# Ports.net
KiCad netlist of a schematic drawn in Altium Designer
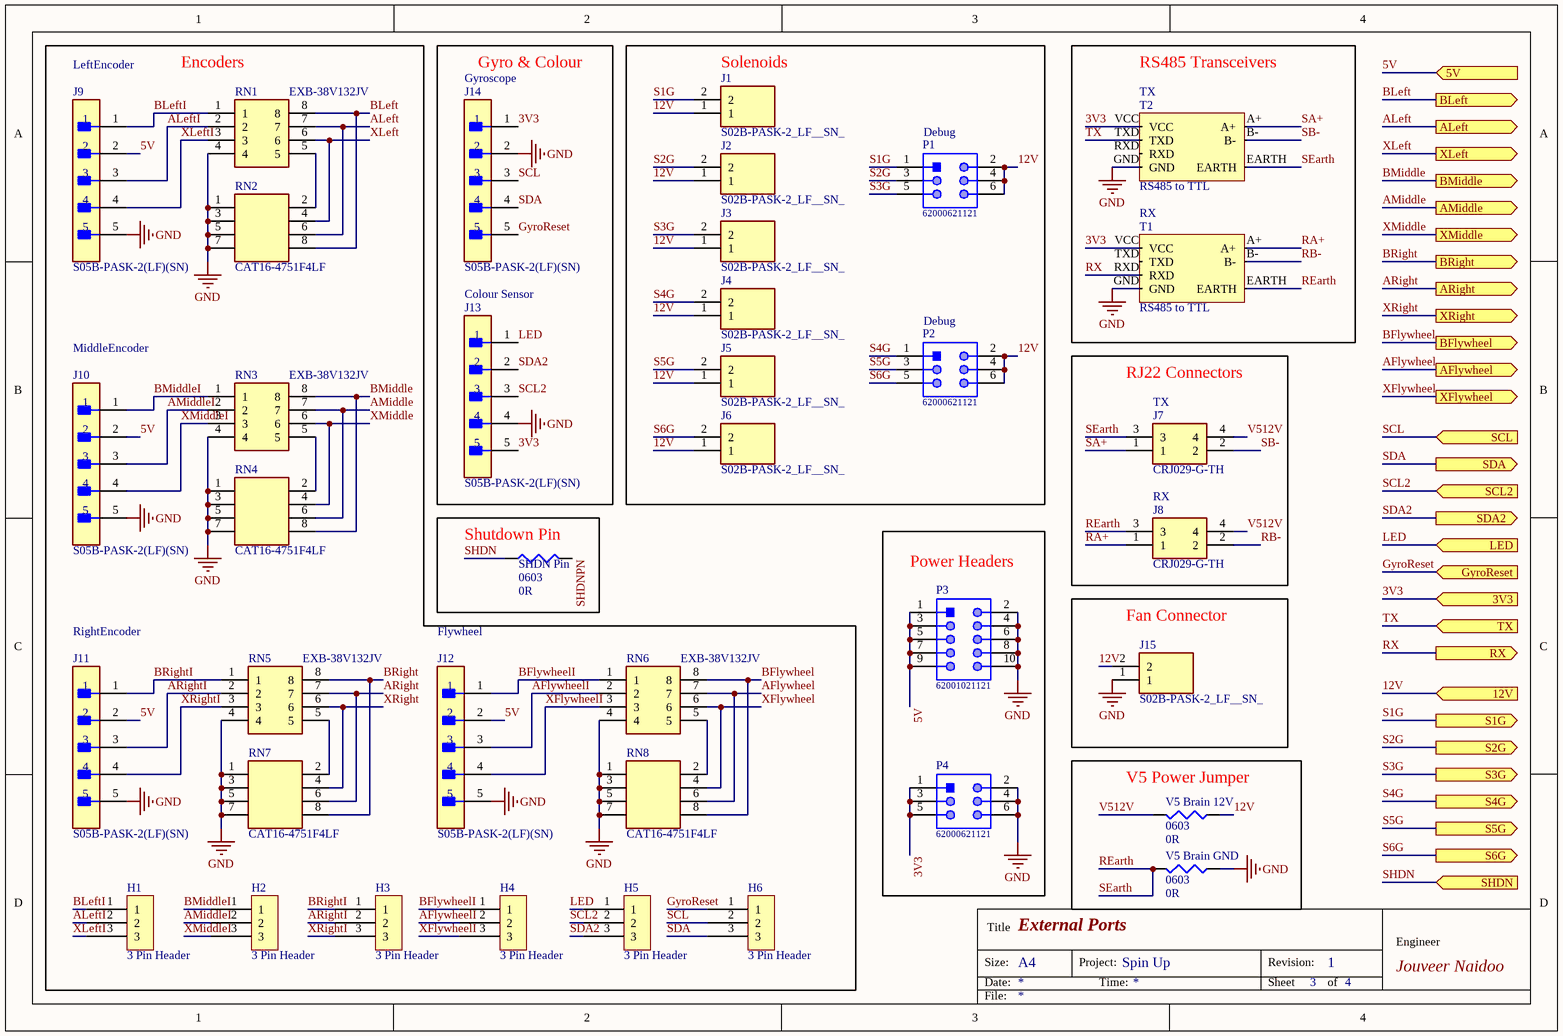
[diagram p0: Ports.SchDoc]

(export (version "E")
  (design (tool "Eeschema 10.0.6"))
  (components
    (comp (ref "H1")
      (value "3 Pin Header")
      (footprint "3 Pin Header-Footprint-1")
      (libsource (lib "Jouveer") (part "3 Pin Header"))
    )
    (comp (ref "H2")
      (value "3 Pin Header")
      (footprint "3 Pin Header-Footprint-1")
      (libsource (lib "Jouveer") (part "3 Pin Header"))
    )
    (comp (ref "H3")
      (value "3 Pin Header")
      (footprint "3 Pin Header-Footprint-1")
      (libsource (lib "Jouveer") (part "3 Pin Header"))
    )
    (comp (ref "H4")
      (value "3 Pin Header")
      (footprint "3 Pin Header-Footprint-1")
      (libsource (lib "Jouveer") (part "3 Pin Header"))
    )
    (comp (ref "H5")
      (value "3 Pin Header")
      (footprint "3 Pin Header-Footprint-1")
      (libsource (lib "Jouveer") (part "3 Pin Header"))
    )
    (comp (ref "H6")
      (value "3 Pin Header")
      (footprint "3 Pin Header-Footprint-1")
      (libsource (lib "Jouveer") (part "3 Pin Header"))
    )
    (comp (ref "J1")
      (value "S02B-PASK-2_LF__SN_")
      (footprint "SamacSys:S02BPASK2LFSN")
      (description "Connector")
      (fields (field (name "MANUFACTURER_PART_NUMBER") "S02B-PASK-2(LF)(SN)"))
      (libsource (lib "*") (part "S02B-PASK-2_LF__SN_"))
    )
    (comp (ref "J2")
      (value "S02B-PASK-2_LF__SN_")
      (footprint "SamacSys:S02BPASK2LFSN")
      (description "Connector")
      (fields (field (name "MANUFACTURER_PART_NUMBER") "S02B-PASK-2(LF)(SN)"))
      (libsource (lib "*") (part "S02B-PASK-2_LF__SN_"))
    )
    (comp (ref "J3")
      (value "S02B-PASK-2_LF__SN_")
      (footprint "SamacSys:S02BPASK2LFSN")
      (description "Connector")
      (fields (field (name "MANUFACTURER_PART_NUMBER") "S02B-PASK-2(LF)(SN)"))
      (libsource (lib "*") (part "S02B-PASK-2_LF__SN_"))
    )
    (comp (ref "J4")
      (value "S02B-PASK-2_LF__SN_")
      (footprint "SamacSys:S02BPASK2LFSN")
      (description "Connector")
      (fields (field (name "MANUFACTURER_PART_NUMBER") "S02B-PASK-2(LF)(SN)"))
      (libsource (lib "*") (part "S02B-PASK-2_LF__SN_"))
    )
    (comp (ref "J5")
      (value "S02B-PASK-2_LF__SN_")
      (footprint "SamacSys:S02BPASK2LFSN")
      (description "Connector")
      (fields (field (name "MANUFACTURER_PART_NUMBER") "S02B-PASK-2(LF)(SN)"))
      (libsource (lib "*") (part "S02B-PASK-2_LF__SN_"))
    )
    (comp (ref "J6")
      (value "S02B-PASK-2_LF__SN_")
      (footprint "SamacSys:S02BPASK2LFSN")
      (description "Connector")
      (fields (field (name "MANUFACTURER_PART_NUMBER") "S02B-PASK-2(LF)(SN)"))
      (libsource (lib "*") (part "S02B-PASK-2_LF__SN_"))
    )
    (comp (ref "J7")
      (value "CRJ029-G-TH")
      (footprint "SamacSys:CRJ029GTH")
      (description "Connector")
      (fields (field (name "MOUSER PART NUMBER") "490-CRJ029-G-TH"))
      (libsource (lib "*") (part "CRJ029-G-TH"))
    )
    (comp (ref "J8")
      (value "CRJ029-G-TH")
      (footprint "SamacSys:CRJ029GTH")
      (description "Connector")
      (fields (field (name "MOUSER PART NUMBER") "490-CRJ029-G-TH"))
      (libsource (lib "*") (part "CRJ029-G-TH"))
    )
    (comp (ref "J9")
      (value "S05B-PASK-2(LF)(SN)")
      (footprint "FP-S05B-PASK-2_LF_SN-MFG")
      (description "CONN HEADER R/A 5POS 2MM")
      (libsource (lib "Altium Content Vault") (part "bf93c07fd2649a848d0ec8585582aab"))
    )
    (comp (ref "J10")
      (value "S05B-PASK-2(LF)(SN)")
      (footprint "FP-S05B-PASK-2_LF_SN-MFG")
      (description "CONN HEADER R/A 5POS 2MM")
      (libsource (lib "Altium Content Vault") (part "bf93c07fd2649a848d0ec8585582aab"))
    )
    (comp (ref "J11")
      (value "S05B-PASK-2(LF)(SN)")
      (footprint "FP-S05B-PASK-2_LF_SN-MFG")
      (description "CONN HEADER R/A 5POS 2MM")
      (libsource (lib "Altium Content Vault") (part "bf93c07fd2649a848d0ec8585582aab"))
    )
    (comp (ref "J12")
      (value "S05B-PASK-2(LF)(SN)")
      (footprint "FP-S05B-PASK-2_LF_SN-MFG")
      (description "CONN HEADER R/A 5POS 2MM")
      (libsource (lib "Altium Content Vault") (part "bf93c07fd2649a848d0ec8585582aab"))
    )
    (comp (ref "J13")
      (value "S05B-PASK-2(LF)(SN)")
      (footprint "FP-S05B-PASK-2_LF_SN-MFG")
      (description "CONN HEADER R/A 5POS 2MM")
      (libsource (lib "Altium Content Vault") (part "bf93c07fd2649a848d0ec8585582aab"))
    )
    (comp (ref "J14")
      (value "S05B-PASK-2(LF)(SN)")
      (footprint "FP-S05B-PASK-2_LF_SN-MFG")
      (description "CONN HEADER R/A 5POS 2MM")
      (libsource (lib "Altium Content Vault") (part "bf93c07fd2649a848d0ec8585582aab"))
    )
    (comp (ref "J15")
      (value "S02B-PASK-2_LF__SN_")
      (footprint "SamacSys:S02BPASK2LFSN")
      (description "Connector")
      (fields (field (name "MANUFACTURER_PART_NUMBER") "S02B-PASK-2(LF)(SN)"))
      (libsource (lib "*") (part "S02B-PASK-2_LF__SN_"))
    )
    (comp (ref "P1")
      (value "62000621121")
      (footprint "62000621121")
      (description "THT Vertical Pin Header WR-PHD, Pitch 2.00 mm, Dual Row, 6 pins")
      (fields (field (name "MANUFACTURER") "Wurth Elektronik") (field (name "PUBLISHER") "WurthElektronik"))
      (libsource (lib "Altium Content Vault") (part "WE-CN-2P-M-R6"))
    )
    (comp (ref "P2")
      (value "62000621121")
      (footprint "62000621121")
      (description "THT Vertical Pin Header WR-PHD, Pitch 2.00 mm, Dual Row, 6 pins")
      (fields (field (name "MANUFACTURER") "Wurth Elektronik") (field (name "PUBLISHER") "WurthElektronik"))
      (libsource (lib "Altium Content Vault") (part "WE-CN-2P-M-R6"))
    )
    (comp (ref "P3")
      (value "62001021121")
      (footprint "62001021121")
      (description "THT Vertical Pin Header WR-PHD, Pitch 2.00 mm, Dual Row, 10 pins")
      (fields (field (name "MANUFACTURER") "Wurth Elektronik") (field (name "PUBLISHER") "WurthElektronik"))
      (libsource (lib "Altium Content Vault") (part "WE-CN-2P-M-R10"))
    )
    (comp (ref "P4")
      (value "62000621121")
      (footprint "62000621121")
      (description "THT Vertical Pin Header WR-PHD, Pitch 2.00 mm, Dual Row, 6 pins")
      (fields (field (name "MANUFACTURER") "Wurth Elektronik") (field (name "PUBLISHER") "WurthElektronik"))
      (libsource (lib "Altium Content Vault") (part "WE-CN-2P-M-R6"))
    )
    (comp (ref "RN1")
      (value "EXB-38V132JV")
      (footprint "SamacSys:EXB38V132JV")
      (description "Resistor Network")
      (fields (field (name "MOUSER PART NUMBER") "667-EXB-38V132JV"))
      (libsource (lib "*") (part "EXB-38V132JV"))
    )
    (comp (ref "RN2")
      (value "CAT16-4751F4LF")
      (footprint "SamacSys:CAPCAV80P155X320X60-8L")
      (description "Resistor Network")
      (fields (field (name "MOUSER PART NUMBER") "652-CAT16-4751F4LF"))
      (libsource (lib "*") (part "CAT16-4751F4LF"))
    )
    (comp (ref "RN3")
      (value "EXB-38V132JV")
      (footprint "SamacSys:EXB38V132JV")
      (description "Resistor Network")
      (fields (field (name "MOUSER PART NUMBER") "667-EXB-38V132JV"))
      (libsource (lib "*") (part "EXB-38V132JV"))
    )
    (comp (ref "RN4")
      (value "CAT16-4751F4LF")
      (footprint "SamacSys:CAPCAV80P155X320X60-8L")
      (description "Resistor Network")
      (fields (field (name "MOUSER PART NUMBER") "652-CAT16-4751F4LF"))
      (libsource (lib "*") (part "CAT16-4751F4LF"))
    )
    (comp (ref "RN5")
      (value "EXB-38V132JV")
      (footprint "SamacSys:EXB38V132JV")
      (description "Resistor Network")
      (fields (field (name "MOUSER PART NUMBER") "667-EXB-38V132JV"))
      (libsource (lib "*") (part "EXB-38V132JV"))
    )
    (comp (ref "RN6")
      (value "EXB-38V132JV")
      (footprint "SamacSys:EXB38V132JV")
      (description "Resistor Network")
      (fields (field (name "MOUSER PART NUMBER") "667-EXB-38V132JV"))
      (libsource (lib "*") (part "EXB-38V132JV"))
    )
    (comp (ref "RN7")
      (value "CAT16-4751F4LF")
      (footprint "SamacSys:CAPCAV80P155X320X60-8L")
      (description "Resistor Network")
      (fields (field (name "MOUSER PART NUMBER") "652-CAT16-4751F4LF"))
      (libsource (lib "*") (part "CAT16-4751F4LF"))
    )
    (comp (ref "RN8")
      (value "CAT16-4751F4LF")
      (footprint "SamacSys:CAPCAV80P155X320X60-8L")
      (description "Resistor Network")
      (fields (field (name "MOUSER PART NUMBER") "652-CAT16-4751F4LF"))
      (libsource (lib "*") (part "CAT16-4751F4LF"))
    )
    (comp (ref "SHDN Pin")
      (value "0603")
      (footprint "J1-0603")
      (description "Resistor")
      (fields (field (name "ALTIUM_VALUE") "0R") (field (name "PUBLISHER") "Altium Limited"))
      (libsource (lib "Miscellaneous Devices") (part "Res3"))
    )
    (comp (ref "T1")
      (value "RS485 to TTL")
      (footprint "RS485 to TTL-Footprint-1")
      (description "RS485 to TTL Converter")
      (libsource (lib "Jouveer") (part "RS485 to TTL-Symbol-1"))
    )
    (comp (ref "T2")
      (value "RS485 to TTL")
      (footprint "RS485 to TTL-Footprint-1")
      (description "RS485 to TTL Converter")
      (libsource (lib "Jouveer") (part "RS485 to TTL-Symbol-1"))
    )
    (comp (ref "V5 Brain 12V")
      (value "0603")
      (footprint "J1-0603")
      (description "Resistor")
      (fields (field (name "ALTIUM_VALUE") "0R") (field (name "PUBLISHER") "Altium Limited"))
      (libsource (lib "Miscellaneous Devices") (part "Res3"))
    )
    (comp (ref "V5 Brain GND")
      (value "0603")
      (footprint "J1-0603")
      (description "Resistor")
      (fields (field (name "ALTIUM_VALUE") "0R") (field (name "PUBLISHER") "Altium Limited"))
      (libsource (lib "Miscellaneous Devices") (part "Res3"))
    )
  )
  (nets
    (net (code "1") (name "/3V3") (class "Default")
      (node (ref "J13") (pin "5") (pinfunction "5_5") (pintype "passive"))
      (node (ref "J14") (pin "1") (pinfunction "1_1") (pintype "passive"))
      (node (ref "P4") (pin "1") (pinfunction "1_1") (pintype "passive"))
      (node (ref "P4") (pin "3") (pinfunction "3_3") (pintype "passive"))
      (node (ref "P4") (pin "5") (pinfunction "5_5") (pintype "passive"))
      (node (ref "T1") (pin "VCC") (pinfunction "VCC_VCC") (pintype "passive"))
      (node (ref "T2") (pin "VCC") (pinfunction "VCC_VCC") (pintype "passive"))
    )
    (net (code "2") (name "/5V") (class "Default")
      (node (ref "J10") (pin "2") (pinfunction "2_2") (pintype "passive"))
      (node (ref "J11") (pin "2") (pinfunction "2_2") (pintype "passive"))
      (node (ref "J12") (pin "2") (pinfunction "2_2") (pintype "passive"))
      (node (ref "J9") (pin "2") (pinfunction "2_2") (pintype "passive"))
      (node (ref "P3") (pin "1") (pinfunction "1_1") (pintype "passive"))
      (node (ref "P3") (pin "3") (pinfunction "3_3") (pintype "passive"))
      (node (ref "P3") (pin "5") (pinfunction "5_5") (pintype "passive"))
      (node (ref "P3") (pin "7") (pinfunction "7_7") (pintype "passive"))
      (node (ref "P3") (pin "9") (pinfunction "9_9") (pintype "passive"))
    )
    (net (code "3") (name "/12V") (class "Default")
      (node (ref "J1") (pin "1") (pinfunction "1_1") (pintype "passive"))
      (node (ref "J15") (pin "2") (pinfunction "2_2") (pintype "passive"))
      (node (ref "J2") (pin "1") (pinfunction "1_1") (pintype "passive"))
      (node (ref "J3") (pin "1") (pinfunction "1_1") (pintype "passive"))
      (node (ref "J4") (pin "1") (pinfunction "1_1") (pintype "passive"))
      (node (ref "J5") (pin "1") (pinfunction "1_1") (pintype "passive"))
      (node (ref "J6") (pin "1") (pinfunction "1_1") (pintype "passive"))
      (node (ref "P1") (pin "2") (pinfunction "2_2") (pintype "passive"))
      (node (ref "P1") (pin "4") (pinfunction "4_4") (pintype "passive"))
      (node (ref "P1") (pin "6") (pinfunction "6_6") (pintype "passive"))
      (node (ref "P2") (pin "2") (pinfunction "2_2") (pintype "passive"))
      (node (ref "P2") (pin "4") (pinfunction "4_4") (pintype "passive"))
      (node (ref "P2") (pin "6") (pinfunction "6_6") (pintype "passive"))
      (node (ref "V5 Brain 12V") (pin "1") (pinfunction "1_1") (pintype "passive"))
    )
    (net (code "4") (name "/AFlywheel") (class "Default")
      (node (ref "RN6") (pin "7") (pinfunction "7_7") (pintype "passive"))
      (node (ref "RN8") (pin "6") (pinfunction "6_6") (pintype "passive"))
    )
    (net (code "5") (name "/AFlywheelI") (class "Default")
      (node (ref "H4") (pin "2") (pinfunction "2_2") (pintype "passive"))
      (node (ref "J12") (pin "3") (pinfunction "3_3") (pintype "passive"))
      (node (ref "RN6") (pin "2") (pinfunction "2_2") (pintype "passive"))
    )
    (net (code "6") (name "/ALeft") (class "Default")
      (node (ref "RN1") (pin "7") (pinfunction "7_7") (pintype "passive"))
      (node (ref "RN2") (pin "6") (pinfunction "6_6") (pintype "passive"))
    )
    (net (code "7") (name "/ALeftI") (class "Default")
      (node (ref "H1") (pin "2") (pinfunction "2_2") (pintype "passive"))
      (node (ref "J9") (pin "3") (pinfunction "3_3") (pintype "passive"))
      (node (ref "RN1") (pin "2") (pinfunction "2_2") (pintype "passive"))
    )
    (net (code "8") (name "/AMiddle") (class "Default")
      (node (ref "RN3") (pin "7") (pinfunction "7_7") (pintype "passive"))
      (node (ref "RN4") (pin "6") (pinfunction "6_6") (pintype "passive"))
    )
    (net (code "9") (name "/AMiddleI") (class "Default")
      (node (ref "H2") (pin "2") (pinfunction "2_2") (pintype "passive"))
      (node (ref "J10") (pin "3") (pinfunction "3_3") (pintype "passive"))
      (node (ref "RN3") (pin "2") (pinfunction "2_2") (pintype "passive"))
    )
    (net (code "10") (name "/ARight") (class "Default")
      (node (ref "RN5") (pin "7") (pinfunction "7_7") (pintype "passive"))
      (node (ref "RN7") (pin "6") (pinfunction "6_6") (pintype "passive"))
    )
    (net (code "11") (name "/ARightI") (class "Default")
      (node (ref "H3") (pin "2") (pinfunction "2_2") (pintype "passive"))
      (node (ref "J11") (pin "3") (pinfunction "3_3") (pintype "passive"))
      (node (ref "RN5") (pin "2") (pinfunction "2_2") (pintype "passive"))
    )
    (net (code "12") (name "/BFlywheel") (class "Default")
      (node (ref "RN6") (pin "8") (pinfunction "8_8") (pintype "passive"))
      (node (ref "RN8") (pin "8") (pinfunction "8_8") (pintype "passive"))
    )
    (net (code "13") (name "/BFlywheelI") (class "Default")
      (node (ref "H4") (pin "1") (pinfunction "1_1") (pintype "passive"))
      (node (ref "J12") (pin "1") (pinfunction "1_1") (pintype "passive"))
      (node (ref "RN6") (pin "1") (pinfunction "1_1") (pintype "passive"))
    )
    (net (code "14") (name "/BLeft") (class "Default")
      (node (ref "RN1") (pin "8") (pinfunction "8_8") (pintype "passive"))
      (node (ref "RN2") (pin "8") (pinfunction "8_8") (pintype "passive"))
    )
    (net (code "15") (name "/BLeftI") (class "Default")
      (node (ref "H1") (pin "1") (pinfunction "1_1") (pintype "passive"))
      (node (ref "J9") (pin "1") (pinfunction "1_1") (pintype "passive"))
      (node (ref "RN1") (pin "1") (pinfunction "1_1") (pintype "passive"))
    )
    (net (code "16") (name "/BMiddle") (class "Default")
      (node (ref "RN3") (pin "8") (pinfunction "8_8") (pintype "passive"))
      (node (ref "RN4") (pin "8") (pinfunction "8_8") (pintype "passive"))
    )
    (net (code "17") (name "/BMiddleI") (class "Default")
      (node (ref "H2") (pin "1") (pinfunction "1_1") (pintype "passive"))
      (node (ref "J10") (pin "1") (pinfunction "1_1") (pintype "passive"))
      (node (ref "RN3") (pin "1") (pinfunction "1_1") (pintype "passive"))
    )
    (net (code "18") (name "/BRight") (class "Default")
      (node (ref "RN5") (pin "8") (pinfunction "8_8") (pintype "passive"))
      (node (ref "RN7") (pin "8") (pinfunction "8_8") (pintype "passive"))
    )
    (net (code "19") (name "/BRightI") (class "Default")
      (node (ref "H3") (pin "1") (pinfunction "1_1") (pintype "passive"))
      (node (ref "J11") (pin "1") (pinfunction "1_1") (pintype "passive"))
      (node (ref "RN5") (pin "1") (pinfunction "1_1") (pintype "passive"))
    )
    (net (code "20") (name "/GyroReset") (class "Default")
      (node (ref "H6") (pin "1") (pinfunction "1_1") (pintype "passive"))
      (node (ref "J14") (pin "5") (pinfunction "5_5") (pintype "passive"))
    )
    (net (code "21") (name "/LED") (class "Default")
      (node (ref "H5") (pin "1") (pinfunction "1_1") (pintype "passive"))
      (node (ref "J13") (pin "1") (pinfunction "1_1") (pintype "passive"))
    )
    (net (code "22") (name "/RA+") (class "Default")
      (node (ref "J8") (pin "1") (pinfunction "1_1") (pintype "passive"))
      (node (ref "T1") (pin "A+") (pinfunction "A+_A+") (pintype "passive"))
    )
    (net (code "23") (name "/RB-") (class "Default")
      (node (ref "J8") (pin "2") (pinfunction "2_2") (pintype "passive"))
      (node (ref "T1") (pin "B-") (pinfunction "B-_B-") (pintype "passive"))
    )
    (net (code "24") (name "/REarth") (class "Default")
      (node (ref "J7") (pin "3") (pinfunction "3_3") (pintype "passive"))
      (node (ref "J8") (pin "3") (pinfunction "3_3") (pintype "passive"))
      (node (ref "T1") (pin "EARTH") (pinfunction "EARTH_EARTH") (pintype "passive"))
      (node (ref "T2") (pin "EARTH") (pinfunction "EARTH_EARTH") (pintype "passive"))
      (node (ref "V5 Brain GND") (pin "2") (pinfunction "2_2") (pintype "passive"))
    )
    (net (code "25") (name "/RX") (class "Default")
      (node (ref "T1") (pin "RXD") (pinfunction "RXD_RXD") (pintype "passive"))
    )
    (net (code "26") (name "/S1G") (class "Default")
      (node (ref "J1") (pin "2") (pinfunction "2_2") (pintype "passive"))
      (node (ref "P1") (pin "1") (pinfunction "1_1") (pintype "passive"))
    )
    (net (code "27") (name "/S2G") (class "Default")
      (node (ref "J2") (pin "2") (pinfunction "2_2") (pintype "passive"))
      (node (ref "P1") (pin "3") (pinfunction "3_3") (pintype "passive"))
    )
    (net (code "28") (name "/S3G") (class "Default")
      (node (ref "J3") (pin "2") (pinfunction "2_2") (pintype "passive"))
      (node (ref "P1") (pin "5") (pinfunction "5_5") (pintype "passive"))
    )
    (net (code "29") (name "/S4G") (class "Default")
      (node (ref "J4") (pin "2") (pinfunction "2_2") (pintype "passive"))
      (node (ref "P2") (pin "1") (pinfunction "1_1") (pintype "passive"))
    )
    (net (code "30") (name "/S5G") (class "Default")
      (node (ref "J5") (pin "2") (pinfunction "2_2") (pintype "passive"))
      (node (ref "P2") (pin "3") (pinfunction "3_3") (pintype "passive"))
    )
    (net (code "31") (name "/S6G") (class "Default")
      (node (ref "J6") (pin "2") (pinfunction "2_2") (pintype "passive"))
      (node (ref "P2") (pin "5") (pinfunction "5_5") (pintype "passive"))
    )
    (net (code "32") (name "/SA+") (class "Default")
      (node (ref "J7") (pin "1") (pinfunction "1_1") (pintype "passive"))
      (node (ref "T2") (pin "A+") (pinfunction "A+_A+") (pintype "passive"))
    )
    (net (code "33") (name "/SB-") (class "Default")
      (node (ref "J7") (pin "2") (pinfunction "2_2") (pintype "passive"))
      (node (ref "T2") (pin "B-") (pinfunction "B-_B-") (pintype "passive"))
    )
    (net (code "34") (name "/SCL") (class "Default")
      (node (ref "H6") (pin "2") (pinfunction "2_2") (pintype "passive"))
      (node (ref "J14") (pin "3") (pinfunction "3_3") (pintype "passive"))
    )
    (net (code "35") (name "/SCL2") (class "Default")
      (node (ref "H5") (pin "2") (pinfunction "2_2") (pintype "passive"))
      (node (ref "J13") (pin "3") (pinfunction "3_3") (pintype "passive"))
    )
    (net (code "36") (name "/SDA") (class "Default")
      (node (ref "H6") (pin "3") (pinfunction "3_3") (pintype "passive"))
      (node (ref "J14") (pin "4") (pinfunction "4_4") (pintype "passive"))
    )
    (net (code "37") (name "/SDA2") (class "Default")
      (node (ref "H5") (pin "3") (pinfunction "3_3") (pintype "passive"))
      (node (ref "J13") (pin "2") (pinfunction "2_2") (pintype "passive"))
    )
    (net (code "38") (name "/SHDN") (class "Default")
      (node (ref "SHDN Pin") (pin "1") (pinfunction "1_1") (pintype "passive"))
    )
    (net (code "39") (name "/SHDNPN") (class "Default")
      (node (ref "SHDN Pin") (pin "2") (pinfunction "2_2") (pintype "passive"))
    )
    (net (code "40") (name "/TX") (class "Default")
      (node (ref "T2") (pin "TXD") (pinfunction "TXD_TXD") (pintype "passive"))
    )
    (net (code "41") (name "/V512V") (class "Default")
      (node (ref "J7") (pin "4") (pinfunction "4_4") (pintype "passive"))
      (node (ref "J8") (pin "4") (pinfunction "4_4") (pintype "passive"))
      (node (ref "V5 Brain 12V") (pin "2") (pinfunction "2_2") (pintype "passive"))
    )
    (net (code "42") (name "/XFlywheel") (class "Default")
      (node (ref "RN6") (pin "6") (pinfunction "6_6") (pintype "passive"))
      (node (ref "RN8") (pin "4") (pinfunction "4_4") (pintype "passive"))
    )
    (net (code "43") (name "/XFlywheelI") (class "Default")
      (node (ref "H4") (pin "3") (pinfunction "3_3") (pintype "passive"))
      (node (ref "J12") (pin "4") (pinfunction "4_4") (pintype "passive"))
      (node (ref "RN6") (pin "3") (pinfunction "3_3") (pintype "passive"))
    )
    (net (code "44") (name "/XLeft") (class "Default")
      (node (ref "RN1") (pin "6") (pinfunction "6_6") (pintype "passive"))
      (node (ref "RN2") (pin "4") (pinfunction "4_4") (pintype "passive"))
    )
    (net (code "45") (name "/XLeftI") (class "Default")
      (node (ref "H1") (pin "3") (pinfunction "3_3") (pintype "passive"))
      (node (ref "J9") (pin "4") (pinfunction "4_4") (pintype "passive"))
      (node (ref "RN1") (pin "3") (pinfunction "3_3") (pintype "passive"))
    )
    (net (code "46") (name "/XMiddle") (class "Default")
      (node (ref "RN3") (pin "6") (pinfunction "6_6") (pintype "passive"))
      (node (ref "RN4") (pin "4") (pinfunction "4_4") (pintype "passive"))
    )
    (net (code "47") (name "/XMiddleI") (class "Default")
      (node (ref "H2") (pin "3") (pinfunction "3_3") (pintype "passive"))
      (node (ref "J10") (pin "4") (pinfunction "4_4") (pintype "passive"))
      (node (ref "RN3") (pin "3") (pinfunction "3_3") (pintype "passive"))
    )
    (net (code "48") (name "/XRight") (class "Default")
      (node (ref "RN5") (pin "6") (pinfunction "6_6") (pintype "passive"))
      (node (ref "RN7") (pin "4") (pinfunction "4_4") (pintype "passive"))
    )
    (net (code "49") (name "/XRightI") (class "Default")
      (node (ref "H3") (pin "3") (pinfunction "3_3") (pintype "passive"))
      (node (ref "J11") (pin "4") (pinfunction "4_4") (pintype "passive"))
      (node (ref "RN5") (pin "3") (pinfunction "3_3") (pintype "passive"))
    )
    (net (code "50") (name "GND") (class "Default")
      (node (ref "J10") (pin "5") (pinfunction "5_5") (pintype "passive"))
      (node (ref "J11") (pin "5") (pinfunction "5_5") (pintype "passive"))
      (node (ref "J12") (pin "5") (pinfunction "5_5") (pintype "passive"))
      (node (ref "J13") (pin "4") (pinfunction "4_4") (pintype "passive"))
      (node (ref "J14") (pin "2") (pinfunction "2_2") (pintype "passive"))
      (node (ref "J15") (pin "1") (pinfunction "1_1") (pintype "passive"))
      (node (ref "J9") (pin "5") (pinfunction "5_5") (pintype "passive"))
      (node (ref "P3") (pin "10") (pinfunction "10_10") (pintype "passive"))
      (node (ref "P3") (pin "2") (pinfunction "2_2") (pintype "passive"))
      (node (ref "P3") (pin "4") (pinfunction "4_4") (pintype "passive"))
      (node (ref "P3") (pin "6") (pinfunction "6_6") (pintype "passive"))
      (node (ref "P3") (pin "8") (pinfunction "8_8") (pintype "passive"))
      (node (ref "P4") (pin "2") (pinfunction "2_2") (pintype "passive"))
      (node (ref "P4") (pin "4") (pinfunction "4_4") (pintype "passive"))
      (node (ref "P4") (pin "6") (pinfunction "6_6") (pintype "passive"))
      (node (ref "RN1") (pin "4") (pinfunction "4_4") (pintype "passive"))
      (node (ref "RN2") (pin "1") (pinfunction "1_1") (pintype "passive"))
      (node (ref "RN2") (pin "3") (pinfunction "3_3") (pintype "passive"))
      (node (ref "RN2") (pin "5") (pinfunction "5_5") (pintype "passive"))
      (node (ref "RN2") (pin "7") (pinfunction "7_7") (pintype "passive"))
      (node (ref "RN3") (pin "4") (pinfunction "4_4") (pintype "passive"))
      (node (ref "RN4") (pin "1") (pinfunction "1_1") (pintype "passive"))
      (node (ref "RN4") (pin "3") (pinfunction "3_3") (pintype "passive"))
      (node (ref "RN4") (pin "5") (pinfunction "5_5") (pintype "passive"))
      (node (ref "RN4") (pin "7") (pinfunction "7_7") (pintype "passive"))
      (node (ref "RN5") (pin "4") (pinfunction "4_4") (pintype "passive"))
      (node (ref "RN6") (pin "4") (pinfunction "4_4") (pintype "passive"))
      (node (ref "RN7") (pin "1") (pinfunction "1_1") (pintype "passive"))
      (node (ref "RN7") (pin "3") (pinfunction "3_3") (pintype "passive"))
      (node (ref "RN7") (pin "5") (pinfunction "5_5") (pintype "passive"))
      (node (ref "RN7") (pin "7") (pinfunction "7_7") (pintype "passive"))
      (node (ref "RN8") (pin "1") (pinfunction "1_1") (pintype "passive"))
      (node (ref "RN8") (pin "3") (pinfunction "3_3") (pintype "passive"))
      (node (ref "RN8") (pin "5") (pinfunction "5_5") (pintype "passive"))
      (node (ref "RN8") (pin "7") (pinfunction "7_7") (pintype "passive"))
      (node (ref "T1") (pin "GND") (pinfunction "GND_GND") (pintype "passive"))
      (node (ref "T2") (pin "GND") (pinfunction "GND_GND") (pintype "passive"))
      (node (ref "V5 Brain GND") (pin "1") (pinfunction "1_1") (pintype "passive"))
    )
    (net (code "51") (name "Net-(RN1-Pad5)") (class "Default")
      (node (ref "RN1") (pin "5") (pinfunction "5_5") (pintype "passive"))
      (node (ref "RN2") (pin "2") (pinfunction "2_2") (pintype "passive"))
    )
    (net (code "52") (name "Net-(RN3-Pad5)") (class "Default")
      (node (ref "RN3") (pin "5") (pinfunction "5_5") (pintype "passive"))
      (node (ref "RN4") (pin "2") (pinfunction "2_2") (pintype "passive"))
    )
    (net (code "53") (name "Net-(RN5-Pad5)") (class "Default")
      (node (ref "RN5") (pin "5") (pinfunction "5_5") (pintype "passive"))
      (node (ref "RN7") (pin "2") (pinfunction "2_2") (pintype "passive"))
    )
    (net (code "54") (name "Net-(RN6-Pad5)") (class "Default")
      (node (ref "RN6") (pin "5") (pinfunction "5_5") (pintype "passive"))
      (node (ref "RN8") (pin "2") (pinfunction "2_2") (pintype "passive"))
    )
    (net (code "55") (name "unconnected-(T1-PadTXD)") (class "Default")
      (node (ref "T1") (pin "TXD") (pinfunction "TXD_TXD") (pintype "passive"))
    )
    (net (code "56") (name "unconnected-(T2-PadRXD)") (class "Default")
      (node (ref "T2") (pin "RXD") (pinfunction "RXD_RXD") (pintype "passive"))
    )
  )
)
